# deadlocks2.net
KiCad netlist of a schematic drawn in EAGLE
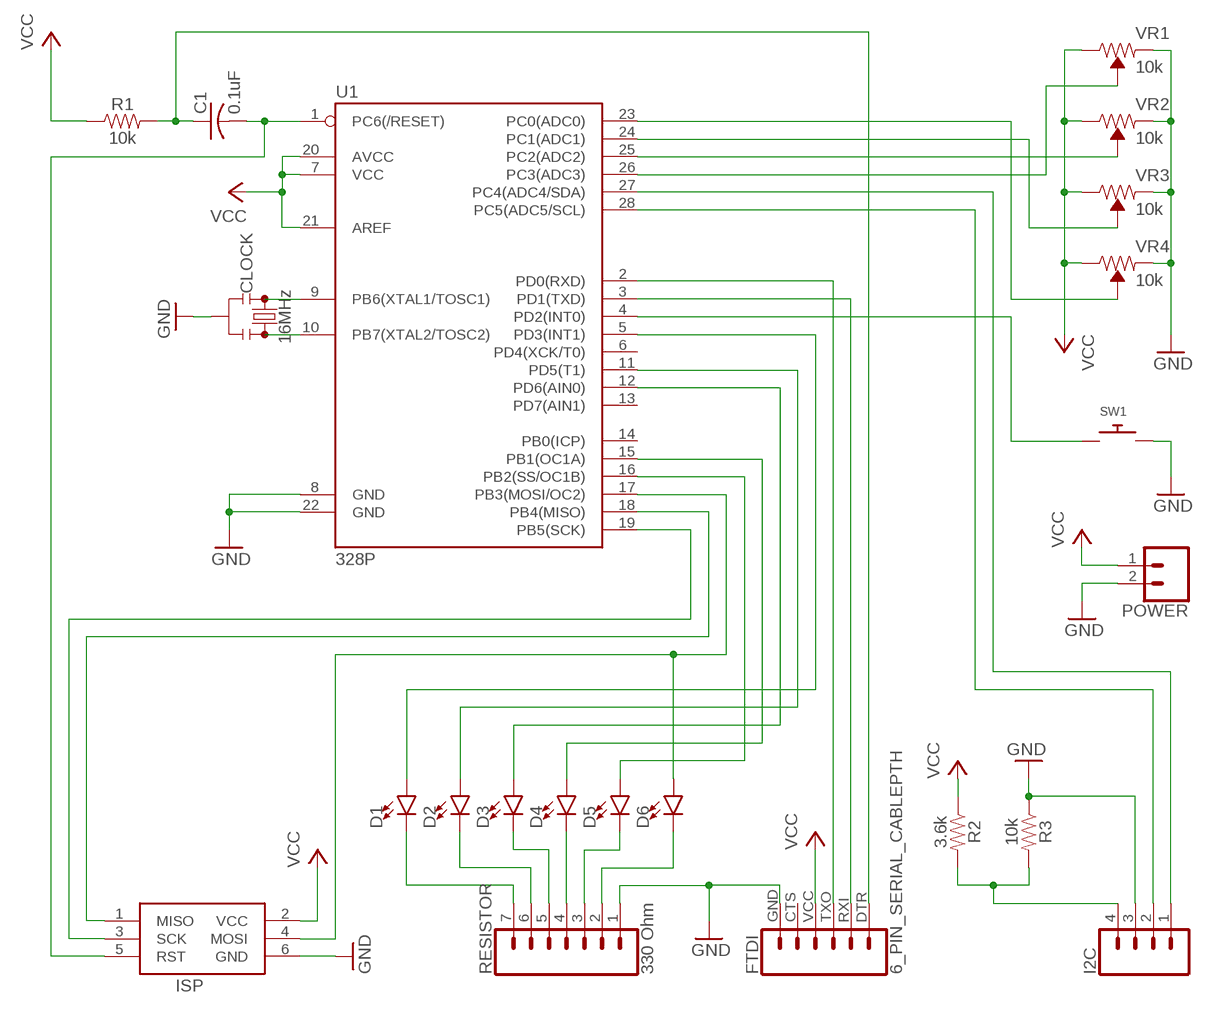
[diagram p0: schematic, sheet 1]

(export (version "E")
  (design (tool "Eeschema 10.0.6"))
  (components
    (comp (ref "C1")
      (value "0.1uF")
      (footprint "eagle-import:C025-024X044")
      (libsource (lib "eagle-import") (part "C-US025-024X044"))
    )
    (comp (ref "CLOCK")
      (value "16MHz")
      (footprint "eagle-import:RESONATOR-PTH-7.6X3.8")
      (libsource (lib "eagle-import") (part "RESONATORPTH-7.6X3.8"))
    )
    (comp (ref "D1")
      (value "LED5MM")
      (footprint "eagle-import:LED_5MM")
      (libsource (lib "eagle-import") (part "LED5MM"))
    )
    (comp (ref "D2")
      (value "LED5MM")
      (footprint "eagle-import:LED_5MM")
      (libsource (lib "eagle-import") (part "LED5MM"))
    )
    (comp (ref "D3")
      (value "LED5MM")
      (footprint "eagle-import:LED_5MM")
      (libsource (lib "eagle-import") (part "LED5MM"))
    )
    (comp (ref "D4")
      (value "LED5MM")
      (footprint "eagle-import:LED_5MM")
      (libsource (lib "eagle-import") (part "LED5MM"))
    )
    (comp (ref "D5")
      (value "LED5MM")
      (footprint "eagle-import:LED_5MM")
      (libsource (lib "eagle-import") (part "LED5MM"))
    )
    (comp (ref "D6")
      (value "LED5MM")
      (footprint "eagle-import:LED_5MM")
      (libsource (lib "eagle-import") (part "LED5MM"))
    )
    (comp (ref "FTDI")
      (value "6_PIN_SERIAL_CABLEPTH")
      (footprint "eagle-import:FTDI_BASIC")
      (libsource (lib "eagle-import") (part "6_PIN_SERIAL_CABLEPTH"))
    )
    (comp (ref "I2C")
      (value "CONN_04")
      (footprint "eagle-import:1X04")
      (libsource (lib "eagle-import") (part "CONN_04"))
    )
    (comp (ref "ISP")
      (value "AVRISP-6")
      (footprint "eagle-import:AVRISP")
      (libsource (lib "eagle-import") (part "AVRISP-6"))
    )
    (comp (ref "POWER")
      (value "CONN_02")
      (footprint "eagle-import:1X02")
      (libsource (lib "eagle-import") (part "CONN_02"))
    )
    (comp (ref "R1")
      (value "10k")
      (footprint "eagle-import:AXIAL-0.3")
      (libsource (lib "eagle-import") (part "10KOHM-HORIZ-1/4W-1%"))
    )
    (comp (ref "R2")
      (value "3.6k")
      (footprint "eagle-import:AXIAL-0.3")
      (libsource (lib "eagle-import") (part "10KOHM-HORIZ-1/4W-1%"))
    )
    (comp (ref "R3")
      (value "10k")
      (footprint "eagle-import:AXIAL-0.3")
      (libsource (lib "eagle-import") (part "10KOHM-HORIZ-1/4W-1%"))
    )
    (comp (ref "RESISTOR")
      (value "330 Ohm")
      (footprint "eagle-import:1X07")
      (libsource (lib "eagle-import") (part "CONN_07"))
    )
    (comp (ref "SW1")
      (value "SWITCH_PUSHBUTTONEVQ-PE")
      (footprint "eagle-import:TACT_PANA-EVQ")
      (libsource (lib "eagle-import") (part "SWITCH_PUSHBUTTONEVQ-PE"))
    )
    (comp (ref "U1")
      (value "328P")
      (footprint "eagle-import:DIP28")
      (libsource (lib "eagle-import") (part "ATMEGA328P_PDIP"))
    )
    (comp (ref "VR1")
      (value "10k")
      (footprint "eagle-import:TRIMPOT-PTH-3386U")
      (libsource (lib "eagle-import") (part "TRIMPOT-PTH-10MM-KNOB-1/2W-10%"))
    )
    (comp (ref "VR2")
      (value "10k")
      (footprint "eagle-import:TRIMPOT-PTH-3386U")
      (libsource (lib "eagle-import") (part "TRIMPOT-PTH-10MM-KNOB-1/2W-10%"))
    )
    (comp (ref "VR3")
      (value "10k")
      (footprint "eagle-import:TRIMPOT-PTH-3386U")
      (libsource (lib "eagle-import") (part "TRIMPOT-PTH-10MM-KNOB-1/2W-10%"))
    )
    (comp (ref "VR4")
      (value "10k")
      (footprint "eagle-import:TRIMPOT-PTH-3386U")
      (libsource (lib "eagle-import") (part "TRIMPOT-PTH-10MM-KNOB-1/2W-10%"))
    )
  )
  (nets
    (net (code "1") (name "GND") (class "Default")
      (node (ref "CLOCK") (pin "2") (pinfunction "2_2") (pintype "passive"))
      (node (ref "FTDI") (pin "GND") (pinfunction "6_GND") (pintype "passive"))
      (node (ref "I2C") (pin "3") (pinfunction "3_3") (pintype "passive"))
      (node (ref "ISP") (pin "6") (pinfunction "GND_6") (pintype "power_in"))
      (node (ref "POWER") (pin "2") (pinfunction "2_2") (pintype "passive"))
      (node (ref "R3") (pin "P$1") (pinfunction "1_P$1") (pintype "passive"))
      (node (ref "RESISTOR") (pin "1") (pinfunction "1_1") (pintype "passive"))
      (node (ref "SW1") (pin "P$2") (pinfunction "P$2_P$2") (pintype "passive"))
      (node (ref "U1") (pin "22") (pinfunction "GND_22") (pintype "bidirectional"))
      (node (ref "U1") (pin "8") (pinfunction "GND_8") (pintype "bidirectional"))
      (node (ref "VR1") (pin "1") (pinfunction "CCW_1") (pintype "passive"))
      (node (ref "VR2") (pin "1") (pinfunction "CCW_1") (pintype "passive"))
      (node (ref "VR3") (pin "1") (pinfunction "CCW_1") (pintype "passive"))
      (node (ref "VR4") (pin "1") (pinfunction "CCW_1") (pintype "passive"))
    )
    (net (code "2") (name "Net-(D1-C)") (class "Default")
      (node (ref "D1") (pin "K") (pinfunction "C_K") (pintype "passive"))
      (node (ref "RESISTOR") (pin "7") (pinfunction "7_7") (pintype "passive"))
    )
    (net (code "3") (name "Net-(D2-C)") (class "Default")
      (node (ref "D2") (pin "K") (pinfunction "C_K") (pintype "passive"))
      (node (ref "RESISTOR") (pin "6") (pinfunction "6_6") (pintype "passive"))
    )
    (net (code "4") (name "Net-(D3-C)") (class "Default")
      (node (ref "D3") (pin "K") (pinfunction "C_K") (pintype "passive"))
      (node (ref "RESISTOR") (pin "5") (pinfunction "5_5") (pintype "passive"))
    )
    (net (code "5") (name "Net-(D4-C)") (class "Default")
      (node (ref "D4") (pin "K") (pinfunction "C_K") (pintype "passive"))
      (node (ref "RESISTOR") (pin "4") (pinfunction "4_4") (pintype "passive"))
    )
    (net (code "6") (name "Net-(D5-C)") (class "Default")
      (node (ref "D5") (pin "K") (pinfunction "C_K") (pintype "passive"))
      (node (ref "RESISTOR") (pin "3") (pinfunction "3_3") (pintype "passive"))
    )
    (net (code "7") (name "Net-(D6-C)") (class "Default")
      (node (ref "D6") (pin "K") (pinfunction "C_K") (pintype "passive"))
      (node (ref "RESISTOR") (pin "2") (pinfunction "2_2") (pintype "passive"))
    )
    (net (code "8") (name "Net-(FTDI-1)") (class "Default")
      (node (ref "C1") (pin "1") (pinfunction "1_1") (pintype "passive"))
      (node (ref "FTDI") (pin "DTR") (pinfunction "1_DTR") (pintype "passive"))
      (node (ref "R1") (pin "P$2") (pinfunction "2_P$2") (pintype "passive"))
    )
    (net (code "9") (name "Net-(FTDI-2)") (class "Default")
      (node (ref "FTDI") (pin "RXI") (pinfunction "2_RXI") (pintype "passive"))
      (node (ref "U1") (pin "3") (pinfunction "PD1(TXD)_3") (pintype "bidirectional"))
    )
    (net (code "10") (name "Net-(FTDI-3)") (class "Default")
      (node (ref "FTDI") (pin "TXO") (pinfunction "3_TXO") (pintype "passive"))
      (node (ref "U1") (pin "2") (pinfunction "PD0(RXD)_2") (pintype "bidirectional"))
    )
    (net (code "11") (name "Net-(ISP-MISO)") (class "Default")
      (node (ref "ISP") (pin "1") (pinfunction "MISO_1") (pintype "input"))
      (node (ref "U1") (pin "18") (pinfunction "PB4(MISO)_18") (pintype "bidirectional"))
    )
    (net (code "12") (name "Net-(ISP-MOSI)") (class "Default")
      (node (ref "D6") (pin "A") (pinfunction "A_A") (pintype "passive"))
      (node (ref "ISP") (pin "4") (pinfunction "MOSI_4") (pintype "output"))
      (node (ref "U1") (pin "17") (pinfunction "PB3(MOSI/OC2)_17") (pintype "bidirectional"))
    )
    (net (code "13") (name "Net-(ISP-RST)") (class "Default")
      (node (ref "C1") (pin "2") (pinfunction "2_2") (pintype "passive"))
      (node (ref "ISP") (pin "5") (pinfunction "RST_5") (pintype "output"))
      (node (ref "U1") (pin "1") (pinfunction "PC6(/RESET)_1") (pintype "bidirectional"))
    )
    (net (code "14") (name "Net-(ISP-SCK)") (class "Default")
      (node (ref "ISP") (pin "3") (pinfunction "SCK_3") (pintype "output"))
      (node (ref "U1") (pin "19") (pinfunction "PB5(SCK)_19") (pintype "bidirectional"))
    )
    (net (code "15") (name "Net-(R2-2)") (class "Default")
      (node (ref "I2C") (pin "4") (pinfunction "4_4") (pintype "passive"))
      (node (ref "R2") (pin "P$2") (pinfunction "2_P$2") (pintype "passive"))
      (node (ref "R3") (pin "P$2") (pinfunction "2_P$2") (pintype "passive"))
    )
    (net (code "16") (name "Net-(U1-PB1(OC1A))") (class "Default")
      (node (ref "D4") (pin "A") (pinfunction "A_A") (pintype "passive"))
      (node (ref "U1") (pin "15") (pinfunction "PB1(OC1A)_15") (pintype "bidirectional"))
    )
    (net (code "17") (name "Net-(U1-PB2(SS{slash}OC1B))") (class "Default")
      (node (ref "D5") (pin "A") (pinfunction "A_A") (pintype "passive"))
      (node (ref "U1") (pin "16") (pinfunction "PB2(SS/OC1B)_16") (pintype "bidirectional"))
    )
    (net (code "18") (name "Net-(U1-PB6(XTAL1{slash}TOSC1))") (class "Default")
      (node (ref "CLOCK") (pin "1") (pinfunction "1_1") (pintype "passive"))
      (node (ref "U1") (pin "9") (pinfunction "PB6(XTAL1/TOSC1)_9") (pintype "bidirectional"))
    )
    (net (code "19") (name "Net-(U1-PB7(XTAL2{slash}TOSC2))") (class "Default")
      (node (ref "CLOCK") (pin "3") (pinfunction "3_3") (pintype "passive"))
      (node (ref "U1") (pin "10") (pinfunction "PB7(XTAL2/TOSC2)_10") (pintype "bidirectional"))
    )
    (net (code "20") (name "Net-(U1-PC0(ADC0))") (class "Default")
      (node (ref "U1") (pin "23") (pinfunction "PC0(ADC0)_23") (pintype "bidirectional"))
      (node (ref "VR4") (pin "2") (pinfunction "WIPER_2") (pintype "passive"))
    )
    (net (code "21") (name "Net-(U1-PC1(ADC1))") (class "Default")
      (node (ref "U1") (pin "24") (pinfunction "PC1(ADC1)_24") (pintype "bidirectional"))
      (node (ref "VR3") (pin "2") (pinfunction "WIPER_2") (pintype "passive"))
    )
    (net (code "22") (name "Net-(U1-PC2(ADC2))") (class "Default")
      (node (ref "U1") (pin "25") (pinfunction "PC2(ADC2)_25") (pintype "bidirectional"))
      (node (ref "VR2") (pin "2") (pinfunction "WIPER_2") (pintype "passive"))
    )
    (net (code "23") (name "Net-(U1-PC3(ADC3))") (class "Default")
      (node (ref "U1") (pin "26") (pinfunction "PC3(ADC3)_26") (pintype "bidirectional"))
      (node (ref "VR1") (pin "2") (pinfunction "WIPER_2") (pintype "passive"))
    )
    (net (code "24") (name "Net-(U1-PC4(ADC4{slash}SDA))") (class "Default")
      (node (ref "I2C") (pin "1") (pinfunction "1_1") (pintype "passive"))
      (node (ref "U1") (pin "27") (pinfunction "PC4(ADC4/SDA)_27") (pintype "bidirectional"))
    )
    (net (code "25") (name "Net-(U1-PC5(ADC5{slash}SCL))") (class "Default")
      (node (ref "I2C") (pin "2") (pinfunction "2_2") (pintype "passive"))
      (node (ref "U1") (pin "28") (pinfunction "PC5(ADC5/SCL)_28") (pintype "bidirectional"))
    )
    (net (code "26") (name "Net-(U1-PD2(INT0))") (class "Default")
      (node (ref "SW1") (pin "P$1") (pinfunction "P$1_P$1") (pintype "passive"))
      (node (ref "U1") (pin "4") (pinfunction "PD2(INT0)_4") (pintype "bidirectional"))
    )
    (net (code "27") (name "Net-(U1-PD3(INT1))") (class "Default")
      (node (ref "D1") (pin "A") (pinfunction "A_A") (pintype "passive"))
      (node (ref "U1") (pin "5") (pinfunction "PD3(INT1)_5") (pintype "bidirectional"))
    )
    (net (code "28") (name "Net-(U1-PD5(T1))") (class "Default")
      (node (ref "D2") (pin "A") (pinfunction "A_A") (pintype "passive"))
      (node (ref "U1") (pin "11") (pinfunction "PD5(T1)_11") (pintype "bidirectional"))
    )
    (net (code "29") (name "Net-(U1-PD6(AIN0))") (class "Default")
      (node (ref "D3") (pin "A") (pinfunction "A_A") (pintype "passive"))
      (node (ref "U1") (pin "12") (pinfunction "PD6(AIN0)_12") (pintype "bidirectional"))
    )
    (net (code "30") (name "VCC") (class "Default")
      (node (ref "FTDI") (pin "VCC") (pinfunction "4_VCC") (pintype "passive"))
      (node (ref "ISP") (pin "2") (pinfunction "VCC_2") (pintype "power_in"))
      (node (ref "POWER") (pin "1") (pinfunction "1_1") (pintype "passive"))
      (node (ref "R1") (pin "P$1") (pinfunction "1_P$1") (pintype "passive"))
      (node (ref "R2") (pin "P$1") (pinfunction "1_P$1") (pintype "passive"))
      (node (ref "U1") (pin "20") (pinfunction "AVCC_20") (pintype "bidirectional"))
      (node (ref "U1") (pin "21") (pinfunction "AREF_21") (pintype "bidirectional"))
      (node (ref "U1") (pin "7") (pinfunction "VCC_7") (pintype "bidirectional"))
      (node (ref "VR1") (pin "3") (pinfunction "CW_3") (pintype "passive"))
      (node (ref "VR2") (pin "3") (pinfunction "CW_3") (pintype "passive"))
      (node (ref "VR3") (pin "3") (pinfunction "CW_3") (pintype "passive"))
      (node (ref "VR4") (pin "3") (pinfunction "CW_3") (pintype "passive"))
    )
    (net (code "31") (name "unconnected-(FTDI-5-PadCTS)") (class "Default")
      (node (ref "FTDI") (pin "CTS") (pinfunction "5_CTS") (pintype "passive"))
    )
    (net (code "32") (name "unconnected-(U1-PB0(ICP)-Pad14)") (class "Default")
      (node (ref "U1") (pin "14") (pinfunction "PB0(ICP)_14") (pintype "bidirectional"))
    )
    (net (code "33") (name "unconnected-(U1-PD4(XCK{slash}T0)-Pad6)") (class "Default")
      (node (ref "U1") (pin "6") (pinfunction "PD4(XCK/T0)_6") (pintype "bidirectional"))
    )
    (net (code "34") (name "unconnected-(U1-PD7(AIN1)-Pad13)") (class "Default")
      (node (ref "U1") (pin "13") (pinfunction "PD7(AIN1)_13") (pintype "bidirectional"))
    )
  )
)
